# SinCos_Acondicionation.net
KiCad netlist of a schematic drawn in Altium Designer
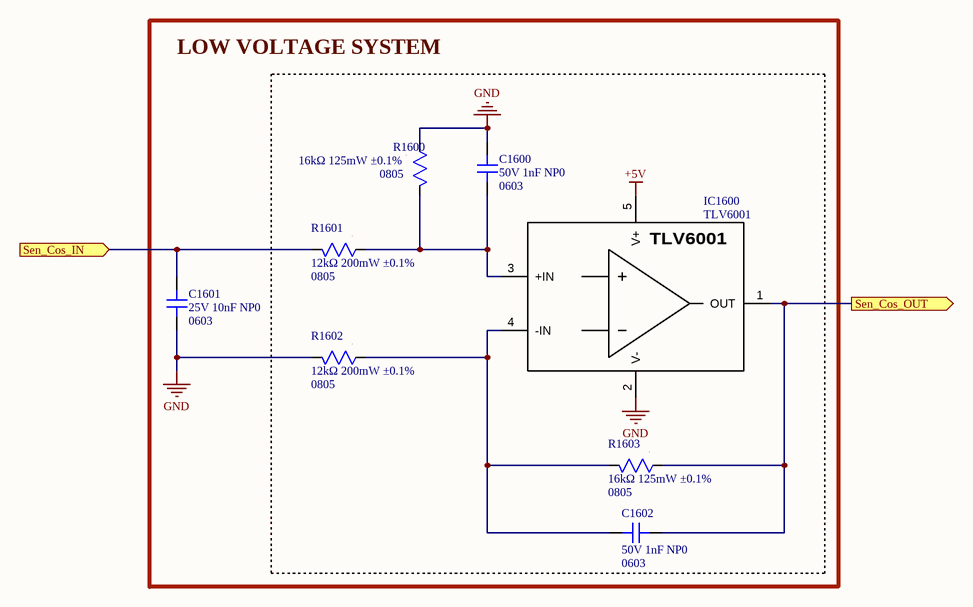
[diagram p0: SinCos_Acondicionation.SchDoc]

(export (version "E")
  (design (tool "Eeschema 10.0.6"))
  (components
    (comp (ref "C1600")
      (value "50V 1nF NP0")
      (footprint "CAP SMD 0603")
      (description "Condensadores de cerámica multicapa (MLCC- SMD/SMT) WCAP-CSGP 1000pF 0603 5% 50V MLCC")
      (fields
        (field (name "PACKAGE") "0603")
        (field (name "MPN") "885012006063")
        (field (name "MANUFACTURER") "Wurth Elektronik")
      )
      (libsource (lib "eUSR_Database") (part "CAP non polarized"))
    )
    (comp (ref "C1601")
      (value "25V 10nF NP0")
      (footprint "CAP SMD 0603")
      (description "Condensadores de cerámica multicapa (MLCC- SMD/SMT) 50V 5100pF 0603 C0G 1%")
      (fields
        (field (name "PACKAGE") "0603")
        (field (name "MPN") "C0603C512F5GACTU")
        (field (name "MANUFACTURER") "KEMET")
      )
      (libsource (lib "eUSR_Database") (part "CAP non polarized"))
    )
    (comp (ref "C1602")
      (value "50V 1nF NP0")
      (footprint "CAP SMD 0603")
      (description "Condensadores de cerámica multicapa (MLCC- SMD/SMT) WCAP-CSGP 1000pF 0603 5% 50V MLCC")
      (fields
        (field (name "PACKAGE") "0603")
        (field (name "MPN") "885012006063")
        (field (name "MANUFACTURER") "Wurth Elektronik")
      )
      (libsource (lib "eUSR_Database") (part "CAP non polarized"))
    )
    (comp (ref "IC1600")
      (value "TLV6001")
      (footprint "SOT-23-5")
      (fields (field (name "MPN") "TLV6001UIDBVR") (field (name "MANUFACTURER") "Texas Instruments"))
      (libsource (lib "eUSR_Database") (part "TLV6001"))
    )
    (comp (ref "R1600")
      (value "16kΩ 125mW ±0.1%")
      (footprint "RES SMD 0805")
      (description "Resistores de película fina - SMD 0805 16Kohm 0.1% 10ppm AEC-Q200")
      (fields
        (field (name "PACKAGE") "0805")
        (field (name "MPN") "ERA-6ARB163V")
        (field (name "MANUFACTURER") "Panasonic")
      )
      (libsource (lib "eUSR_Database") (part "RES"))
    )
    (comp (ref "R1601")
      (value "12kΩ 200mW ±0.1%")
      (footprint "RES SMD 0805")
      (description "Resistores de película fina - SMD RQ 0805 12K1 0.1% 10PPM 5K RL")
      (fields
        (field (name "PACKAGE") "0805")
        (field (name "MPN") "RQ73C2A12K1BTD")
        (field (name "MANUFACTURER") "TE Connectivity / Holsworthy")
      )
      (libsource (lib "eUSR_Database") (part "RES"))
    )
    (comp (ref "R1602")
      (value "12kΩ 200mW ±0.1%")
      (footprint "RES SMD 0805")
      (description "Resistores de película fina - SMD RQ 0805 12K1 0.1% 10PPM 5K RL")
      (fields
        (field (name "PACKAGE") "0805")
        (field (name "MPN") "RQ73C2A12K1BTD")
        (field (name "MANUFACTURER") "TE Connectivity / Holsworthy")
      )
      (libsource (lib "eUSR_Database") (part "RES"))
    )
    (comp (ref "R1603")
      (value "16kΩ 125mW ±0.1%")
      (footprint "RES SMD 0805")
      (description "Resistores de película fina - SMD 0805 16Kohm 0.1% 10ppm AEC-Q200")
      (fields
        (field (name "PACKAGE") "0805")
        (field (name "MPN") "ERA-6ARB163V")
        (field (name "MANUFACTURER") "Panasonic")
      )
      (libsource (lib "eUSR_Database") (part "RES"))
    )
  )
  (nets
    (net (code "1") (name "+5V") (class "Default")
      (node (ref "IC1600") (pin "5") (pinfunction "V+_5") (pintype "passive"))
    )
    (net (code "2") (name "/Sen_Cos_IN") (class "Default")
      (node (ref "C1601") (pin "1") (pinfunction "1_1") (pintype "passive"))
      (node (ref "R1601") (pin "2") (pinfunction "2_2") (pintype "passive"))
    )
    (net (code "3") (name "/Sen_Cos_OUT") (class "Default")
      (node (ref "C1602") (pin "2") (pinfunction "2_2") (pintype "passive"))
      (node (ref "IC1600") (pin "1") (pinfunction "OUT_1") (pintype "passive"))
      (node (ref "R1603") (pin "1") (pinfunction "1_1") (pintype "passive"))
    )
    (net (code "4") (name "GND") (class "Default")
      (node (ref "C1600") (pin "2") (pinfunction "2_2") (pintype "passive"))
      (node (ref "C1601") (pin "2") (pinfunction "2_2") (pintype "passive"))
      (node (ref "IC1600") (pin "2") (pinfunction "V-_2") (pintype "passive"))
      (node (ref "R1600") (pin "1") (pinfunction "1_1") (pintype "passive"))
      (node (ref "R1602") (pin "2") (pinfunction "2_2") (pintype "passive"))
    )
    (net (code "5") (name "Net-(IC1600-+IN)") (class "Default")
      (node (ref "C1600") (pin "1") (pinfunction "1_1") (pintype "passive"))
      (node (ref "IC1600") (pin "3") (pinfunction "+IN_3") (pintype "passive"))
      (node (ref "R1600") (pin "2") (pinfunction "2_2") (pintype "passive"))
      (node (ref "R1601") (pin "1") (pinfunction "1_1") (pintype "passive"))
    )
    (net (code "6") (name "Net-(IC1600--IN)") (class "Default")
      (node (ref "C1602") (pin "1") (pinfunction "1_1") (pintype "passive"))
      (node (ref "IC1600") (pin "4") (pinfunction "-IN_4") (pintype "passive"))
      (node (ref "R1602") (pin "1") (pinfunction "1_1") (pintype "passive"))
      (node (ref "R1603") (pin "2") (pinfunction "2_2") (pintype "passive"))
    )
  )
)
